# CAN.net
KiCad netlist of a schematic drawn in Altium Designer
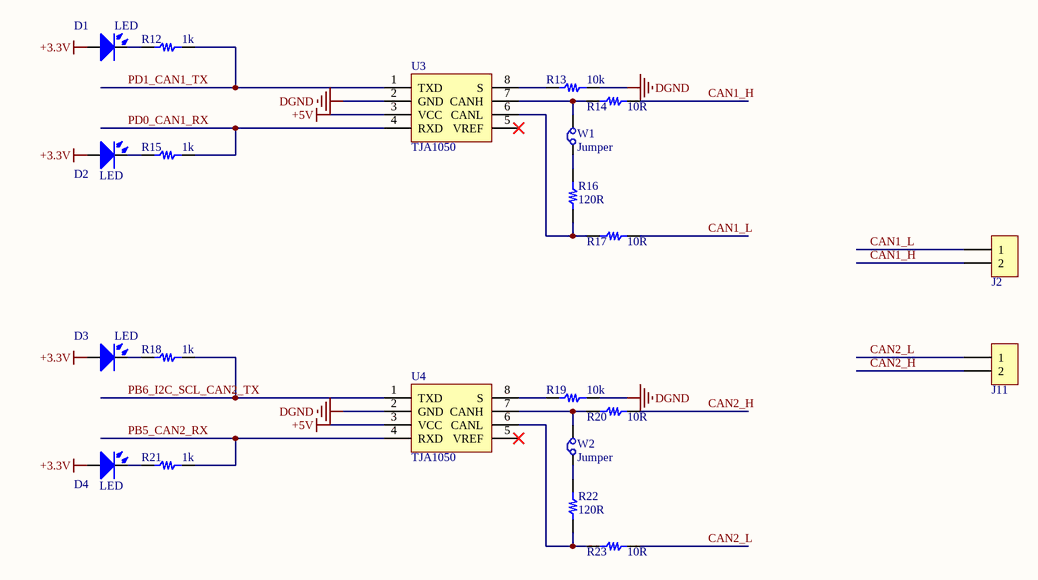
[diagram p0: CAN.SchDoc]

(export (version "E")
  (design (tool "Eeschema 10.0.6"))
  (components
    (comp (ref "D1")
      (value "LED")
      (footprint "0805-LED-RED")
      (description "Typical INFRARED GaAs LED")
      (fields (field (name "PUBLISHER") "Altium Limited"))
      (libsource (lib "Device_CHT") (part "LED"))
    )
    (comp (ref "D2")
      (value "LED")
      (footprint "0805-LED-RED")
      (description "Typical INFRARED GaAs LED")
      (fields (field (name "PUBLISHER") "Altium Limited"))
      (libsource (lib "Device_CHT") (part "LED"))
    )
    (comp (ref "D3")
      (value "LED")
      (footprint "0805-LED-RED")
      (description "Typical INFRARED GaAs LED")
      (fields (field (name "PUBLISHER") "Altium Limited"))
      (libsource (lib "Device_CHT") (part "LED"))
    )
    (comp (ref "D4")
      (value "LED")
      (footprint "0805-LED-RED")
      (description "Typical INFRARED GaAs LED")
      (fields (field (name "PUBLISHER") "Altium Limited"))
      (libsource (lib "Device_CHT") (part "LED"))
    )
    (comp (ref "J2")
      (value "CON2")
      (footprint "XH2.54-2P")
      (description "Connector")
      (libsource (lib "Connector_Veiko") (part "CON2"))
    )
    (comp (ref "J11")
      (value "CON2")
      (footprint "XH2.54-2P")
      (description "Connector")
      (libsource (lib "Connector_Veiko") (part "CON2"))
    )
    (comp (ref "R12")
      (value "1k")
      (footprint "0805_small")
      (description "电阻")
      (fields (field (name "PUBLISHER") "Altium Limited"))
      (libsource (lib "Device_CHT") (part "Res"))
    )
    (comp (ref "R13")
      (value "10k")
      (footprint "0805_small")
      (description "电阻")
      (fields (field (name "PUBLISHER") "Altium Limited"))
      (libsource (lib "Device_CHT") (part "Res"))
    )
    (comp (ref "R14")
      (value "10R")
      (footprint "0805_small")
      (description "电阻")
      (fields (field (name "PUBLISHER") "Altium Limited"))
      (libsource (lib "Device_CHT") (part "Res"))
    )
    (comp (ref "R15")
      (value "1k")
      (footprint "0805_small")
      (description "电阻")
      (fields (field (name "PUBLISHER") "Altium Limited"))
      (libsource (lib "Device_CHT") (part "Res"))
    )
    (comp (ref "R16")
      (value "120R")
      (footprint "0805_small")
      (description "电阻")
      (fields (field (name "PUBLISHER") "Altium Limited"))
      (libsource (lib "Device_CHT") (part "Res"))
    )
    (comp (ref "R17")
      (value "10R")
      (footprint "0805_small")
      (description "电阻")
      (fields (field (name "PUBLISHER") "Altium Limited"))
      (libsource (lib "Device_CHT") (part "Res"))
    )
    (comp (ref "R18")
      (value "1k")
      (footprint "0805_small")
      (description "电阻")
      (fields (field (name "PUBLISHER") "Altium Limited"))
      (libsource (lib "Device_CHT") (part "Res"))
    )
    (comp (ref "R19")
      (value "10k")
      (footprint "0805_small")
      (description "电阻")
      (fields (field (name "PUBLISHER") "Altium Limited"))
      (libsource (lib "Device_CHT") (part "Res"))
    )
    (comp (ref "R20")
      (value "10R")
      (footprint "0805_small")
      (description "电阻")
      (fields (field (name "PUBLISHER") "Altium Limited"))
      (libsource (lib "Device_CHT") (part "Res"))
    )
    (comp (ref "R21")
      (value "1k")
      (footprint "0805_small")
      (description "电阻")
      (fields (field (name "PUBLISHER") "Altium Limited"))
      (libsource (lib "Device_CHT") (part "Res"))
    )
    (comp (ref "R22")
      (value "120R")
      (footprint "0805_small")
      (description "电阻")
      (fields (field (name "PUBLISHER") "Altium Limited"))
      (libsource (lib "Device_CHT") (part "Res"))
    )
    (comp (ref "R23")
      (value "10R")
      (footprint "0805_small")
      (description "电阻")
      (fields (field (name "PUBLISHER") "Altium Limited"))
      (libsource (lib "Device_CHT") (part "Res"))
    )
    (comp (ref "U3") (value "TJA1050") (footprint "SO-8") (libsource (lib "Device_CHT") (part "TJA1050")))
    (comp (ref "U4") (value "TJA1050") (footprint "SO-8") (libsource (lib "Device_CHT") (part "TJA1050")))
    (comp (ref "W1")
      (value "Jumper")
      (footprint "0603_jump_Pad")
      (description "Jumper Wire")
      (fields (field (name "PUBLISHER") "Altium Limited"))
      (libsource (lib "Connector_Veiko") (part "Jumper"))
    )
    (comp (ref "W2")
      (value "Jumper")
      (footprint "0603_jump_Pad")
      (description "Jumper Wire")
      (fields (field (name "PUBLISHER") "Altium Limited"))
      (libsource (lib "Connector_Veiko") (part "Jumper"))
    )
  )
  (nets
    (net (code "1") (name "+3.3V") (class "Default")
      (node (ref "D1") (pin "1") (pinfunction "A_1") (pintype "passive"))
      (node (ref "D2") (pin "1") (pinfunction "A_1") (pintype "passive"))
      (node (ref "D3") (pin "1") (pinfunction "A_1") (pintype "passive"))
      (node (ref "D4") (pin "1") (pinfunction "A_1") (pintype "passive"))
    )
    (net (code "2") (name "+5V") (class "Default")
      (node (ref "U3") (pin "3") (pinfunction "VCC_3") (pintype "passive"))
      (node (ref "U4") (pin "3") (pinfunction "VCC_3") (pintype "passive"))
    )
    (net (code "3") (name "/CAN1_H") (class "Default")
      (node (ref "J2") (pin "2") (pinfunction "2_2") (pintype "passive"))
      (node (ref "R14") (pin "2") (pinfunction "2_2") (pintype "passive"))
    )
    (net (code "4") (name "/CAN1_L") (class "Default")
      (node (ref "J2") (pin "1") (pinfunction "1_1") (pintype "passive"))
      (node (ref "R17") (pin "2") (pinfunction "2_2") (pintype "passive"))
    )
    (net (code "5") (name "/CAN2_H") (class "Default")
      (node (ref "J11") (pin "2") (pinfunction "2_2") (pintype "passive"))
      (node (ref "R20") (pin "2") (pinfunction "2_2") (pintype "passive"))
    )
    (net (code "6") (name "/CAN2_L") (class "Default")
      (node (ref "J11") (pin "1") (pinfunction "1_1") (pintype "passive"))
      (node (ref "R23") (pin "2") (pinfunction "2_2") (pintype "passive"))
    )
    (net (code "7") (name "/PB5_CAN2_RX") (class "Default")
      (node (ref "R21") (pin "1") (pinfunction "1_1") (pintype "passive"))
      (node (ref "U4") (pin "4") (pinfunction "RXD_4") (pintype "passive"))
    )
    (net (code "8") (name "/PB6_I2C_SCL_CAN2_TX") (class "Default")
      (node (ref "R18") (pin "1") (pinfunction "1_1") (pintype "passive"))
      (node (ref "U4") (pin "1") (pinfunction "TXD_1") (pintype "passive"))
    )
    (net (code "9") (name "/PD0_CAN1_RX") (class "Default")
      (node (ref "R15") (pin "1") (pinfunction "1_1") (pintype "passive"))
      (node (ref "U3") (pin "4") (pinfunction "RXD_4") (pintype "passive"))
    )
    (net (code "10") (name "/PD1_CAN1_TX") (class "Default")
      (node (ref "R12") (pin "1") (pinfunction "1_1") (pintype "passive"))
      (node (ref "U3") (pin "1") (pinfunction "TXD_1") (pintype "passive"))
    )
    (net (code "11") (name "DGND") (class "Default")
      (node (ref "R13") (pin "1") (pinfunction "1_1") (pintype "passive"))
      (node (ref "R19") (pin "1") (pinfunction "1_1") (pintype "passive"))
      (node (ref "U3") (pin "2") (pinfunction "GND_2") (pintype "passive"))
      (node (ref "U4") (pin "2") (pinfunction "GND_2") (pintype "passive"))
    )
    (net (code "12") (name "Net-(D1-K)") (class "Default")
      (node (ref "D1") (pin "2") (pinfunction "K_2") (pintype "passive"))
      (node (ref "R12") (pin "2") (pinfunction "2_2") (pintype "passive"))
    )
    (net (code "13") (name "Net-(D2-K)") (class "Default")
      (node (ref "D2") (pin "2") (pinfunction "K_2") (pintype "passive"))
      (node (ref "R15") (pin "2") (pinfunction "2_2") (pintype "passive"))
    )
    (net (code "14") (name "Net-(D3-K)") (class "Default")
      (node (ref "D3") (pin "2") (pinfunction "K_2") (pintype "passive"))
      (node (ref "R18") (pin "2") (pinfunction "2_2") (pintype "passive"))
    )
    (net (code "15") (name "Net-(D4-K)") (class "Default")
      (node (ref "D4") (pin "2") (pinfunction "K_2") (pintype "passive"))
      (node (ref "R21") (pin "2") (pinfunction "2_2") (pintype "passive"))
    )
    (net (code "16") (name "Net-(U3-CANH)") (class "Default")
      (node (ref "R14") (pin "1") (pinfunction "1_1") (pintype "passive"))
      (node (ref "U3") (pin "7") (pinfunction "CANH_7") (pintype "passive"))
      (node (ref "W1") (pin "2") (pinfunction "C2_2") (pintype "passive"))
    )
    (net (code "17") (name "Net-(U3-CANL)") (class "Default")
      (node (ref "R16") (pin "2") (pinfunction "2_2") (pintype "passive"))
      (node (ref "R17") (pin "1") (pinfunction "1_1") (pintype "passive"))
      (node (ref "U3") (pin "6") (pinfunction "CANL_6") (pintype "passive"))
    )
    (net (code "18") (name "Net-(U3-S)") (class "Default")
      (node (ref "R13") (pin "2") (pinfunction "2_2") (pintype "passive"))
      (node (ref "U3") (pin "8") (pinfunction "S_8") (pintype "passive"))
    )
    (net (code "19") (name "Net-(U4-CANH)") (class "Default")
      (node (ref "R20") (pin "1") (pinfunction "1_1") (pintype "passive"))
      (node (ref "U4") (pin "7") (pinfunction "CANH_7") (pintype "passive"))
      (node (ref "W2") (pin "2") (pinfunction "C2_2") (pintype "passive"))
    )
    (net (code "20") (name "Net-(U4-CANL)") (class "Default")
      (node (ref "R22") (pin "2") (pinfunction "2_2") (pintype "passive"))
      (node (ref "R23") (pin "1") (pinfunction "1_1") (pintype "passive"))
      (node (ref "U4") (pin "6") (pinfunction "CANL_6") (pintype "passive"))
    )
    (net (code "21") (name "Net-(U4-S)") (class "Default")
      (node (ref "R19") (pin "2") (pinfunction "2_2") (pintype "passive"))
      (node (ref "U4") (pin "8") (pinfunction "S_8") (pintype "passive"))
    )
    (net (code "22") (name "Net-(W1-C1)") (class "Default")
      (node (ref "R16") (pin "1") (pinfunction "1_1") (pintype "passive"))
      (node (ref "W1") (pin "1") (pinfunction "C1_1") (pintype "passive"))
    )
    (net (code "23") (name "Net-(W2-C1)") (class "Default")
      (node (ref "R22") (pin "1") (pinfunction "1_1") (pintype "passive"))
      (node (ref "W2") (pin "1") (pinfunction "C1_1") (pintype "passive"))
    )
    (net (code "24") (name "unconnected-(U3-VREF-Pad5)") (class "Default")
      (node (ref "U3") (pin "5") (pinfunction "VREF_5") (pintype "passive+no_connect"))
    )
    (net (code "25") (name "unconnected-(U4-VREF-Pad5)") (class "Default")
      (node (ref "U4") (pin "5") (pinfunction "VREF_5") (pintype "passive+no_connect"))
    )
  )
)
